# S05_Display.net
KiCad netlist of a schematic drawn in Altium Designer
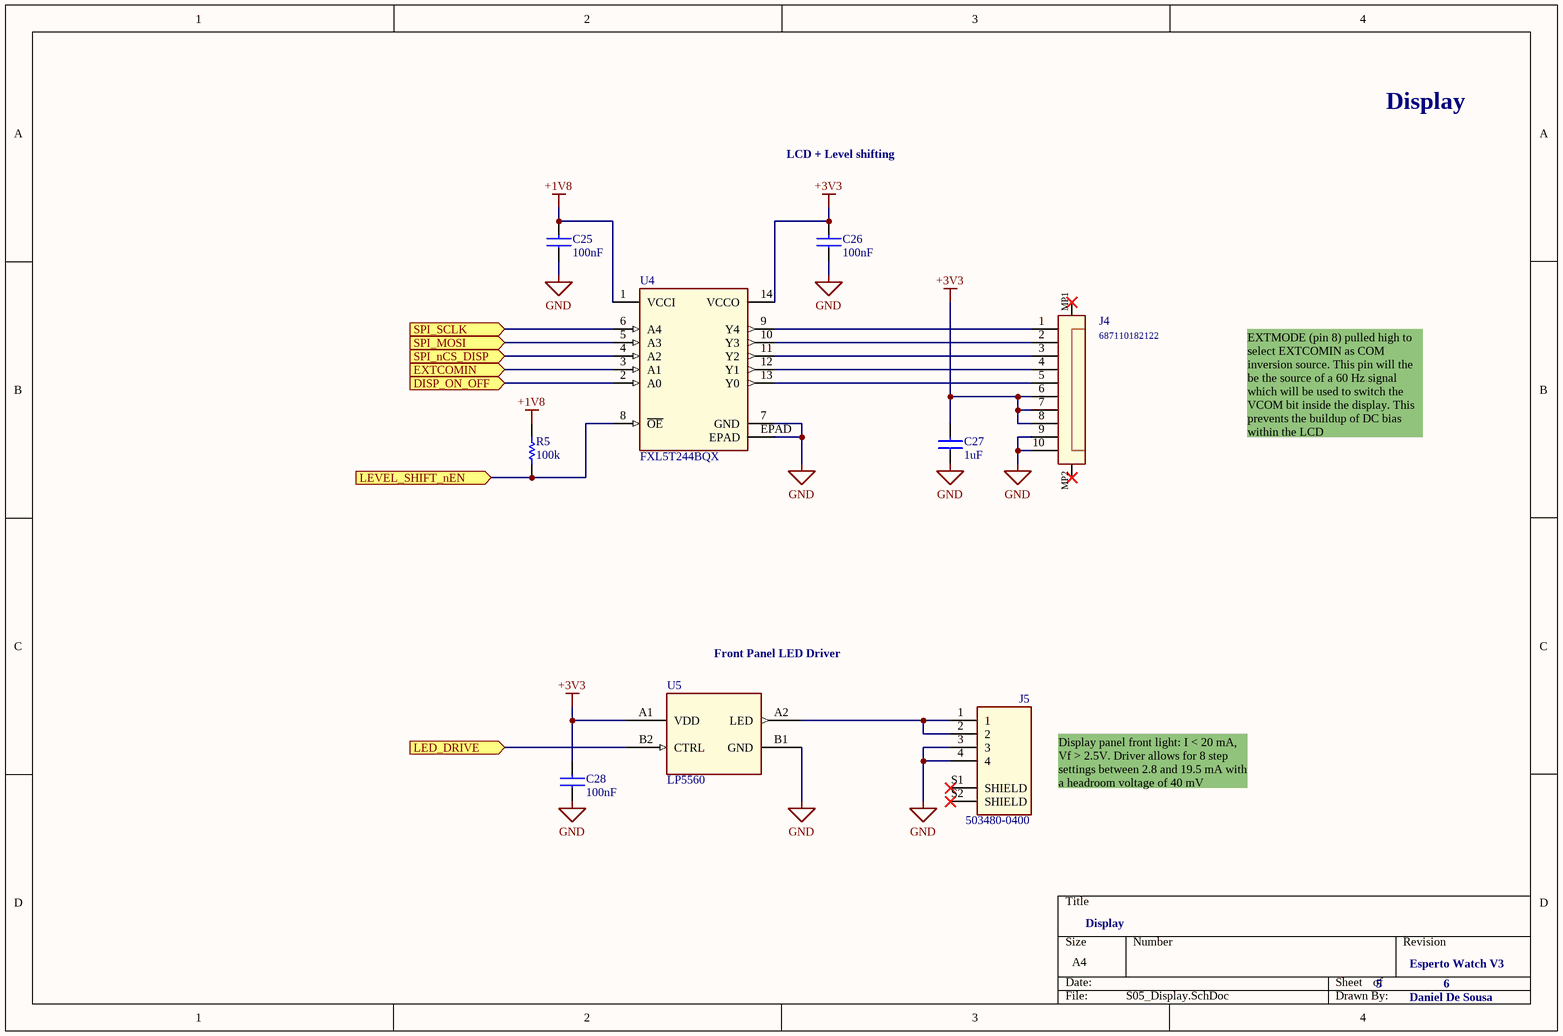
[diagram p0: S05_Display.SchDoc]

(export (version "E")
  (design (tool "Eeschema 10.0.6"))
  (components
    (comp (ref "C25")
      (value "100nF")
      (footprint "CC_1005_0402_N")
      (description "Capacitor")
      (libsource (lib "Esperto") (part "Capacitor"))
    )
    (comp (ref "C26")
      (value "100nF")
      (footprint "CC_1005_0402_N")
      (description "Capacitor")
      (libsource (lib "Esperto") (part "Capacitor"))
    )
    (comp (ref "C27")
      (value "1uF")
      (footprint "CC_1005_0402_N")
      (description "Capacitor")
      (libsource (lib "Esperto") (part "Capacitor"))
    )
    (comp (ref "C28")
      (value "100nF")
      (footprint "CC_1005_0402_N")
      (description "Capacitor")
      (libsource (lib "Esperto") (part "Capacitor"))
    )
    (comp (ref "J4")
      (value "687110182122")
      (footprint "687110182122")
      (description "SMT ZIF Connectors WR-FPC, Horizontal, Back Locking Dual Contact, pitch 0.5 mm, 10 pins")
      (fields (field (name "PUBLISHER") "Wurth Elektronik"))
      (libsource (lib "Esperto") (part "687110182122"))
    )
    (comp (ref "J5")
      (value "503480-0400")
      (footprint "503480-0400")
      (description "0.50mm Pitch Easy-On")
      (fields (field (name "MP") "5034800400") (field (name "DIGI-KEY_PART_NUMBER") "WM1386CT-ND"))
      (libsource (lib "Esperto") (part "503480-0400"))
    )
    (comp (ref "R5")
      (value "100k")
      (footprint "RC_1005_0402_N")
      (description "Resistor")
      (libsource (lib "Esperto") (part "Resistor"))
    )
    (comp (ref "U4")
      (value "FXL5T244BQX")
      (footprint "FXL5T244BQX")
      (description "Voltage Level Translator Unidirectional 1 Circuit 5 Channel")
      (fields (field (name "MF") "ON Semiconductor") (field (name "DIGI-KEY_PART_NUMBER") "FXLA108BQXCT-ND"))
      (libsource (lib "Esperto") (part "FXL5T244BQX"))
    )
    (comp (ref "U5")
      (value "LP5560")
      (footprint "LP5560")
      (description "Programmable Single-LED Driver")
      (fields
        (field (name "MANUFACTURER_PART_NUMBER") "LP5522TM/NOPB")
        (field (name "COPYRIGHT") "Copyright (C) 2018 Accelerated Designs. All rights reserved")
      )
      (libsource (lib "Esperto") (part "LP5560"))
    )
  )
  (nets
    (net (code "1") (name "+1V8") (class "Default")
      (node (ref "C25") (pin "2") (pinfunction "2_2") (pintype "passive"))
      (node (ref "R5") (pin "2") (pinfunction "2_2") (pintype "passive"))
      (node (ref "U4") (pin "1") (pinfunction "VCCI_1") (pintype "power_in"))
    )
    (net (code "2") (name "+3V3") (class "Default")
      (node (ref "C26") (pin "2") (pinfunction "2_2") (pintype "passive"))
      (node (ref "C27") (pin "2") (pinfunction "2_2") (pintype "passive"))
      (node (ref "C28") (pin "2") (pinfunction "2_2") (pintype "passive"))
      (node (ref "J4") (pin "6") (pinfunction "6_6") (pintype "passive"))
      (node (ref "J4") (pin "7") (pinfunction "7_7") (pintype "passive"))
      (node (ref "J4") (pin "8") (pinfunction "8_8") (pintype "passive"))
      (node (ref "U4") (pin "14") (pinfunction "VCCO_14") (pintype "power_in"))
      (node (ref "U5") (pin "A1") (pinfunction "VDD_A1") (pintype "power_in"))
    )
    (net (code "3") (name "/DISP_ON_OFF") (class "Default")
      (node (ref "U4") (pin "2") (pinfunction "A0_2") (pintype "input"))
    )
    (net (code "4") (name "/EXTCOMIN") (class "Default")
      (node (ref "U4") (pin "3") (pinfunction "A1_3") (pintype "input"))
    )
    (net (code "5") (name "/LED_DRIVE") (class "Default")
      (node (ref "U5") (pin "B2") (pinfunction "CTRL_B2") (pintype "input"))
    )
    (net (code "6") (name "/LEVEL_SHIFT_nEN") (class "Default")
      (node (ref "R5") (pin "1") (pinfunction "1_1") (pintype "passive"))
      (node (ref "U4") (pin "8") (pinfunction "~{OE}_8") (pintype "input"))
    )
    (net (code "7") (name "/SPI_MOSI") (class "Default")
      (node (ref "U4") (pin "5") (pinfunction "A3_5") (pintype "input"))
    )
    (net (code "8") (name "/SPI_SCLK") (class "Default")
      (node (ref "U4") (pin "6") (pinfunction "A4_6") (pintype "input"))
    )
    (net (code "9") (name "/SPI_nCS_DISP") (class "Default")
      (node (ref "U4") (pin "4") (pinfunction "A2_4") (pintype "input"))
    )
    (net (code "10") (name "GND") (class "Default")
      (node (ref "C25") (pin "1") (pinfunction "1_1") (pintype "passive"))
      (node (ref "C26") (pin "1") (pinfunction "1_1") (pintype "passive"))
      (node (ref "C27") (pin "1") (pinfunction "1_1") (pintype "passive"))
      (node (ref "C28") (pin "1") (pinfunction "1_1") (pintype "passive"))
      (node (ref "J4") (pin "10") (pinfunction "10_10") (pintype "passive"))
      (node (ref "J4") (pin "9") (pinfunction "9_9") (pintype "passive"))
      (node (ref "J5") (pin "3") (pinfunction "3_3") (pintype "passive"))
      (node (ref "J5") (pin "4") (pinfunction "4_4") (pintype "passive"))
      (node (ref "U4") (pin "7") (pinfunction "GND_7") (pintype "power_in"))
      (node (ref "U4") (pin "EPAD") (pinfunction "EPAD_EPAD") (pintype "power_in"))
      (node (ref "U5") (pin "B1") (pinfunction "GND_B1") (pintype "power_in"))
    )
    (net (code "11") (name "Net-(U4-Y0)") (class "Default")
      (node (ref "J4") (pin "5") (pinfunction "5_5") (pintype "passive"))
      (node (ref "U4") (pin "13") (pinfunction "Y0_13") (pintype "output"))
    )
    (net (code "12") (name "Net-(U4-Y1)") (class "Default")
      (node (ref "J4") (pin "4") (pinfunction "4_4") (pintype "passive"))
      (node (ref "U4") (pin "12") (pinfunction "Y1_12") (pintype "output"))
    )
    (net (code "13") (name "Net-(U4-Y2)") (class "Default")
      (node (ref "J4") (pin "3") (pinfunction "3_3") (pintype "passive"))
      (node (ref "U4") (pin "11") (pinfunction "Y2_11") (pintype "output"))
    )
    (net (code "14") (name "Net-(U4-Y3)") (class "Default")
      (node (ref "J4") (pin "2") (pinfunction "2_2") (pintype "passive"))
      (node (ref "U4") (pin "10") (pinfunction "Y3_10") (pintype "output"))
    )
    (net (code "15") (name "Net-(U4-Y4)") (class "Default")
      (node (ref "J4") (pin "1") (pinfunction "1_1") (pintype "passive"))
      (node (ref "U4") (pin "9") (pinfunction "Y4_9") (pintype "output"))
    )
    (net (code "16") (name "Net-(U5-LED)") (class "Default")
      (node (ref "J5") (pin "1") (pinfunction "1_1") (pintype "passive"))
      (node (ref "J5") (pin "2") (pinfunction "2_2") (pintype "passive"))
      (node (ref "U5") (pin "A2") (pinfunction "LED_A2") (pintype "output"))
    )
    (net (code "17") (name "unconnected-(J4-PadMP1)") (class "Default")
      (node (ref "J4") (pin "MP1") (pinfunction "MP1_MP1") (pintype "passive+no_connect"))
    )
    (net (code "18") (name "unconnected-(J4-PadMP2)") (class "Default")
      (node (ref "J4") (pin "MP2") (pinfunction "MP2_MP2") (pintype "passive+no_connect"))
    )
    (net (code "19") (name "unconnected-(J5-SHIELD-PadS1)") (class "Default")
      (node (ref "J5") (pin "S1") (pinfunction "SHIELD_S1") (pintype "passive+no_connect"))
    )
    (net (code "20") (name "unconnected-(J5-SHIELD-PadS2)") (class "Default")
      (node (ref "J5") (pin "S2") (pinfunction "SHIELD_S2") (pintype "passive+no_connect"))
    )
  )
)
